# 14-Power-P1V8.net
KiCad netlist of a schematic drawn in Altium Designer
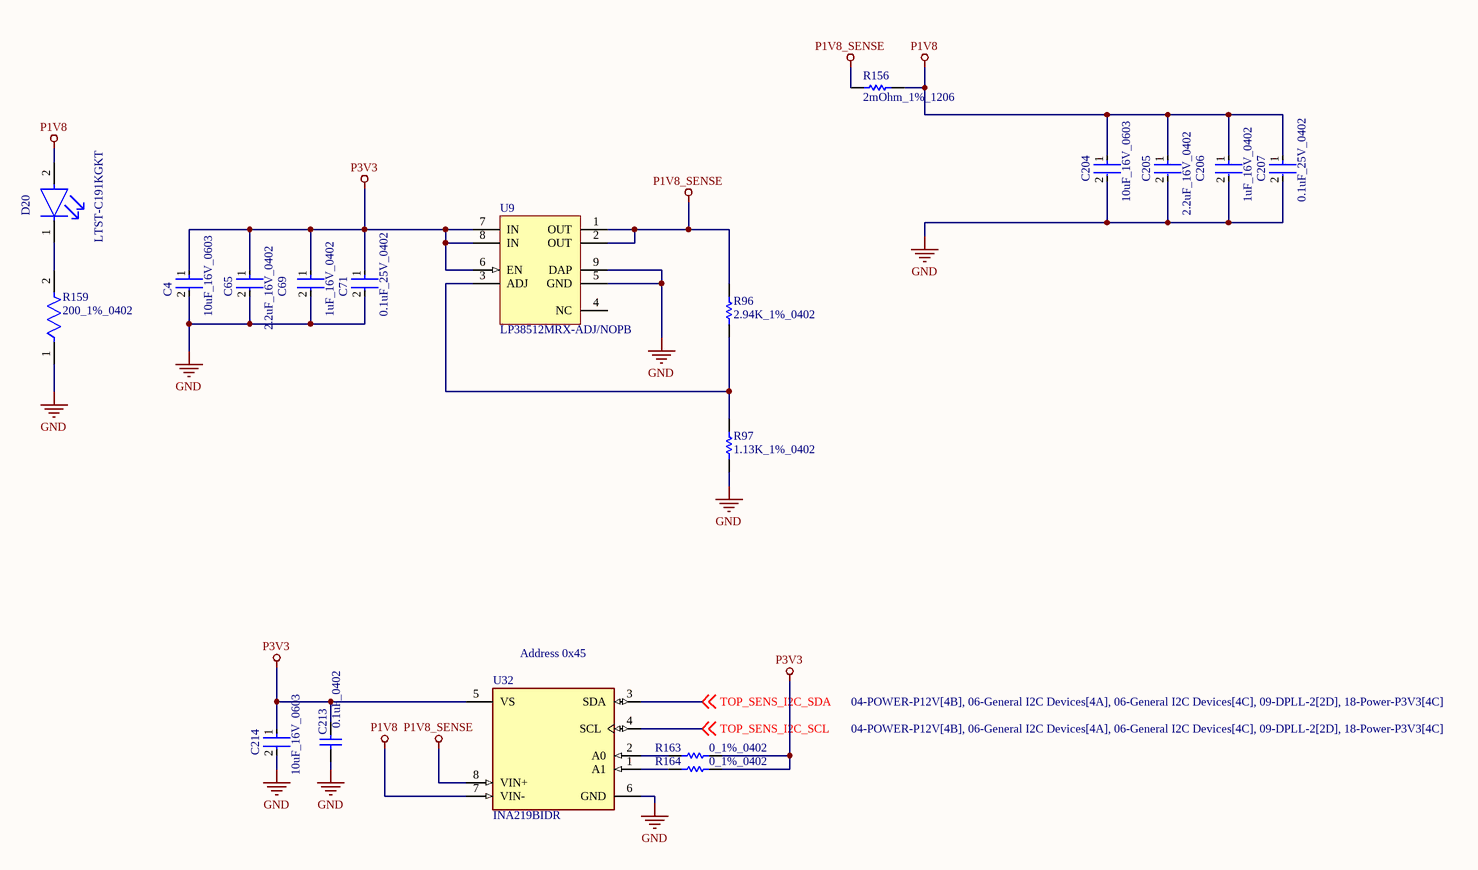
[diagram p0: 14-Power-P1V8.SchDoc]

(export (version "E")
  (design (tool "Eeschema 10.0.6"))
  (components
    (comp (ref "C4")
      (value "10uF_16V_0603")
      (footprint "FP-0603-L_1_6_0_2-W_0_8_0-MFG")
      (description "Multilayer Ceramic Capacitor 10uF 16V X5R 20% SMD 0603 T/R")
      (fields (field (name "TOLERANCE") "20%"))
      (libsource (lib "Altium Content Vault") (part "b4654b650e69147ec39a6b967a45e02"))
    )
    (comp (ref "C65")
      (value "2.2uF_16V_0402")
      (footprint "FP-C1005-050-0_05-IPC_A")
      (description "Multilayer Ceramic Capacitors 2.2μF ±10% 16V X5R SMD 0402")
      (fields (field (name "TOLERANCE") "10%"))
      (libsource (lib "Altium Content Vault") (part "b4654b650e69147ec39a6b967a45e02"))
    )
    (comp (ref "C69")
      (value "1uF_16V_0402")
      (footprint "FP-0402-L_1_0_0_05-W_0_5-IPC_A")
      (description "None")
      (fields (field (name "TOLERANCE") "10%"))
      (libsource (lib "Altium Content Vault") (part "b4654b650e69147ec39a6b967a45e02"))
    )
    (comp (ref "C71")
      (value "0.1uF_25V_0402")
      (footprint "FP-0402-L_1_0_1-W_0_5_0_1-IPC_C")
      (description "General Purpose Ceramic Capacitor, 0402, 100nF, 10%, X7R, 15%, 25V")
      (fields (field (name "VOLTAGE") "25V") (field (name "TOLERANCE") "10%"))
      (libsource (lib "Altium Content Vault") (part "b4654b650e69147ec39a6b967a45e02"))
    )
    (comp (ref "C204")
      (value "10uF_16V_0603")
      (footprint "FP-0603-L_1_6_0_2-W_0_8_0-MFG")
      (description "Multilayer Ceramic Capacitor 10uF 16V X5R 20% SMD 0603 T/R")
      (fields (field (name "TOLERANCE") "20%"))
      (libsource (lib "Altium Content Vault") (part "b4654b650e69147ec39a6b967a45e02"))
    )
    (comp (ref "C205")
      (value "2.2uF_16V_0402")
      (footprint "FP-C1005-050-0_05-IPC_A")
      (description "Multilayer Ceramic Capacitors 2.2μF ±10% 16V X5R SMD 0402")
      (fields (field (name "TOLERANCE") "10%"))
      (libsource (lib "Altium Content Vault") (part "b4654b650e69147ec39a6b967a45e02"))
    )
    (comp (ref "C206")
      (value "1uF_16V_0402")
      (footprint "FP-0402-L_1_0_0_05-W_0_5-IPC_A")
      (description "None")
      (fields (field (name "TOLERANCE") "10%"))
      (libsource (lib "Altium Content Vault") (part "b4654b650e69147ec39a6b967a45e02"))
    )
    (comp (ref "C207")
      (value "0.1uF_25V_0402")
      (footprint "FP-0402-L_1_0_1-W_0_5_0_1-IPC_C")
      (description "General Purpose Ceramic Capacitor, 0402, 100nF, 10%, X7R, 15%, 25V")
      (fields (field (name "VOLTAGE") "25V") (field (name "TOLERANCE") "10%"))
      (libsource (lib "Altium Content Vault") (part "b4654b650e69147ec39a6b967a45e02"))
    )
    (comp (ref "C213")
      (value "0.1uF_0402")
      (footprint "CAPC1005X56X25NL10T15")
      (fields
        (field (name "PART NUMBER") "LD02YD104KAB2A")
        (field (name "MANUFACTURER") "AVX Interconnect / Elco")
      )
      (libsource (lib "Altium Content Vault") (part "CAP"))
    )
    (comp (ref "C214")
      (value "10uF_16V_0603")
      (footprint "FP-0603-L_1_6_0_2-W_0_8_0-MFG")
      (description "Multilayer Ceramic Capacitor 10uF 16V X5R 20% SMD 0603 T/R")
      (fields (field (name "TOLERANCE") "20%"))
      (libsource (lib "Altium Content Vault") (part "b4654b650e69147ec39a6b967a45e02"))
    )
    (comp (ref "D20")
      (value "LTST-C191KGKT")
      (footprint "FP-LTST-C191KGKT-MFG")
      (description "LED GREEN CLEAR SMD")
      (libsource (lib "Altium Content Vault") (part "8706943c75ba83719d021d2fdc84c58"))
    )
    (comp (ref "R96")
      (value "2.94K_1%_0402")
      (footprint "RESC1005X40X25ML05T10")
      (fields (field (name "MANUFACTURER") "Yageo") (field (name "PART NUMBER") "RC0402FR-072K94L"))
      (libsource (lib "Altium Content Vault") (part "RES"))
    )
    (comp (ref "R97")
      (value "1.13K_1%_0402")
      (footprint "RESC1005X40X25NL05T05")
      (fields (field (name "MANUFACTURER") "Panasonic") (field (name "PART NUMBER") "ERJ-2RKF1131X"))
      (libsource (lib "Altium Content Vault") (part "RES"))
    )
    (comp (ref "R156")
      (value "2mOhm_1%_1206")
      (footprint "RESC3216X89X64NL25T25")
      (fields (field (name "MANUFACTURER") "Vishay Dale") (field (name "PART NUMBER") "WSL12062L000FEA18"))
      (libsource (lib "Altium Content Vault") (part "RES"))
    )
    (comp (ref "R159")
      (value "200_1%_0402")
      (footprint "FP-ERJ2RK-IPC_A")
      (description "RES SMD 200 OHM 1% 1/10W 0402")
      (fields (field (name "TOLERANCE") "1%"))
      (libsource (lib "Altium Content Vault") (part "1029c3af85768c4190bb7ad29bc67b5"))
    )
    (comp (ref "R163")
      (value "0_1%_0402")
      (footprint "RESC1005X40X25LL05T05")
      (description "Chip Resistor, 0 Ohm, 0.1 W, -55 to 155 degC, 0402 (1005 Metric), RoHS, Tape and Reel")
      (fields (field (name "MANUFACTURER") "Panasonic") (field (name "TOLERANCE") "5%"))
      (libsource (lib "Altium Content Vault") (part "RES-2"))
    )
    (comp (ref "R164")
      (value "0_1%_0402")
      (footprint "RESC1005X40X25LL05T05")
      (description "Chip Resistor, 0 Ohm, 0.1 W, -55 to 155 degC, 0402 (1005 Metric), RoHS, Tape and Reel")
      (fields (field (name "MANUFACTURER") "Panasonic") (field (name "TOLERANCE") "5%"))
      (libsource (lib "Altium Content Vault") (part "RES-2"))
    )
    (comp (ref "U9")
      (value "LP38512MRX-ADJ/NOPB")
      (footprint "MRA08B_M")
      (description "1.5A Fast-Transient Response Adjustable Low-Dropout Linear Voltage Regulator, 8-pin PSOP, Pb-Free")
      (fields (field (name "MANUFACTURER") "National Semiconductor"))
      (libsource (lib "Altium Content Vault") (part "PM-REG-LP38512MR-IL9"))
    )
    (comp (ref "U32")
      (value "INA219BIDR")
      (footprint "FP-D0008A-MFG")
      (description "IC MONITOR PWR/CURR BIDIR 8-SOIC")
      (libsource (lib "Altium Content Vault") (part "41cc1aee4cbc9fa2660a15773fa0e79"))
    )
  )
  (nets
    (net (code "1") (name "GND") (class "Default")
      (node (ref "C204") (pin "2") (pinfunction "2_2") (pintype "passive"))
      (node (ref "C205") (pin "2") (pinfunction "2_2") (pintype "passive"))
      (node (ref "C206") (pin "2") (pinfunction "2_2") (pintype "passive"))
      (node (ref "C207") (pin "2") (pinfunction "2_2") (pintype "passive"))
      (node (ref "C213") (pin "1") (pinfunction "1_1") (pintype "passive"))
      (node (ref "C214") (pin "2") (pinfunction "2_2") (pintype "passive"))
      (node (ref "C4") (pin "2") (pinfunction "2_2") (pintype "passive"))
      (node (ref "C65") (pin "2") (pinfunction "2_2") (pintype "passive"))
      (node (ref "C69") (pin "2") (pinfunction "2_2") (pintype "passive"))
      (node (ref "C71") (pin "2") (pinfunction "2_2") (pintype "passive"))
      (node (ref "R159") (pin "1") (pinfunction "1_1") (pintype "passive"))
      (node (ref "R97") (pin "1") (pinfunction "1_1") (pintype "passive"))
      (node (ref "U32") (pin "6") (pinfunction "GND_6") (pintype "power_in"))
      (node (ref "U9") (pin "5") (pinfunction "GND_5") (pintype "power_in"))
      (node (ref "U9") (pin "9") (pinfunction "DAP_9") (pintype "passive"))
    )
    (net (code "2") (name "Net-(D20-C)") (class "Default")
      (node (ref "D20") (pin "1") (pinfunction "C_1") (pintype "passive"))
      (node (ref "R159") (pin "2") (pinfunction "2_2") (pintype "passive"))
    )
    (net (code "3") (name "Net-(U9-ADJ)") (class "Default")
      (node (ref "R96") (pin "1") (pinfunction "1_1") (pintype "passive"))
      (node (ref "R97") (pin "2") (pinfunction "2_2") (pintype "passive"))
      (node (ref "U9") (pin "3") (pinfunction "ADJ_3") (pintype "passive"))
    )
    (net (code "4") (name "Net-(U32-A0)") (class "Default")
      (node (ref "R163") (pin "1") (pinfunction "1_1") (pintype "passive"))
      (node (ref "U32") (pin "2") (pinfunction "A0_2") (pintype "input"))
    )
    (net (code "5") (name "Net-(U32-A1)") (class "Default")
      (node (ref "R164") (pin "1") (pinfunction "1_1") (pintype "passive"))
      (node (ref "U32") (pin "1") (pinfunction "A1_1") (pintype "input"))
    )
    (net (code "6") (name "P1V8") (class "Default")
      (node (ref "C204") (pin "1") (pinfunction "1_1") (pintype "passive"))
      (node (ref "C205") (pin "1") (pinfunction "1_1") (pintype "passive"))
      (node (ref "C206") (pin "1") (pinfunction "1_1") (pintype "passive"))
      (node (ref "C207") (pin "1") (pinfunction "1_1") (pintype "passive"))
      (node (ref "D20") (pin "2") (pinfunction "A_2") (pintype "passive"))
      (node (ref "R156") (pin "2") (pinfunction "2_2") (pintype "passive"))
      (node (ref "U32") (pin "7") (pinfunction "VIN-_7") (pintype "input"))
    )
    (net (code "7") (name "P1V8_SENSE") (class "Default")
      (node (ref "R156") (pin "1") (pinfunction "1_1") (pintype "passive"))
      (node (ref "R96") (pin "2") (pinfunction "2_2") (pintype "passive"))
      (node (ref "U32") (pin "8") (pinfunction "VIN+_8") (pintype "input"))
      (node (ref "U9") (pin "1") (pinfunction "OUT_1") (pintype "power_in"))
      (node (ref "U9") (pin "2") (pinfunction "OUT_2") (pintype "power_in"))
    )
    (net (code "8") (name "P3V3") (class "Default")
      (node (ref "C213") (pin "2") (pinfunction "2_2") (pintype "passive"))
      (node (ref "C214") (pin "1") (pinfunction "1_1") (pintype "passive"))
      (node (ref "C4") (pin "1") (pinfunction "1_1") (pintype "passive"))
      (node (ref "C65") (pin "1") (pinfunction "1_1") (pintype "passive"))
      (node (ref "C69") (pin "1") (pinfunction "1_1") (pintype "passive"))
      (node (ref "C71") (pin "1") (pinfunction "1_1") (pintype "passive"))
      (node (ref "R163") (pin "2") (pinfunction "2_2") (pintype "passive"))
      (node (ref "R164") (pin "2") (pinfunction "2_2") (pintype "passive"))
      (node (ref "U32") (pin "5") (pinfunction "VS_5") (pintype "power_in"))
      (node (ref "U9") (pin "6") (pinfunction "EN_6") (pintype "input"))
      (node (ref "U9") (pin "7") (pinfunction "IN_7") (pintype "power_in"))
      (node (ref "U9") (pin "8") (pinfunction "IN_8") (pintype "power_in"))
    )
    (net (code "9") (name "TOP_SENS_I2C_SCL") (class "Default")
      (node (ref "U32") (pin "4") (pinfunction "SCL_4") (pintype "bidirectional"))
    )
    (net (code "10") (name "TOP_SENS_I2C_SDA") (class "Default")
      (node (ref "U32") (pin "3") (pinfunction "SDA_3") (pintype "bidirectional"))
    )
    (net (code "11") (name "unconnected-(U9-NC-Pad4)") (class "Default")
      (node (ref "U9") (pin "4") (pinfunction "NC_4") (pintype "passive"))
    )
  )
)
